# openbook_schematic.net
KiCad netlist of a schematic drawn in EAGLE
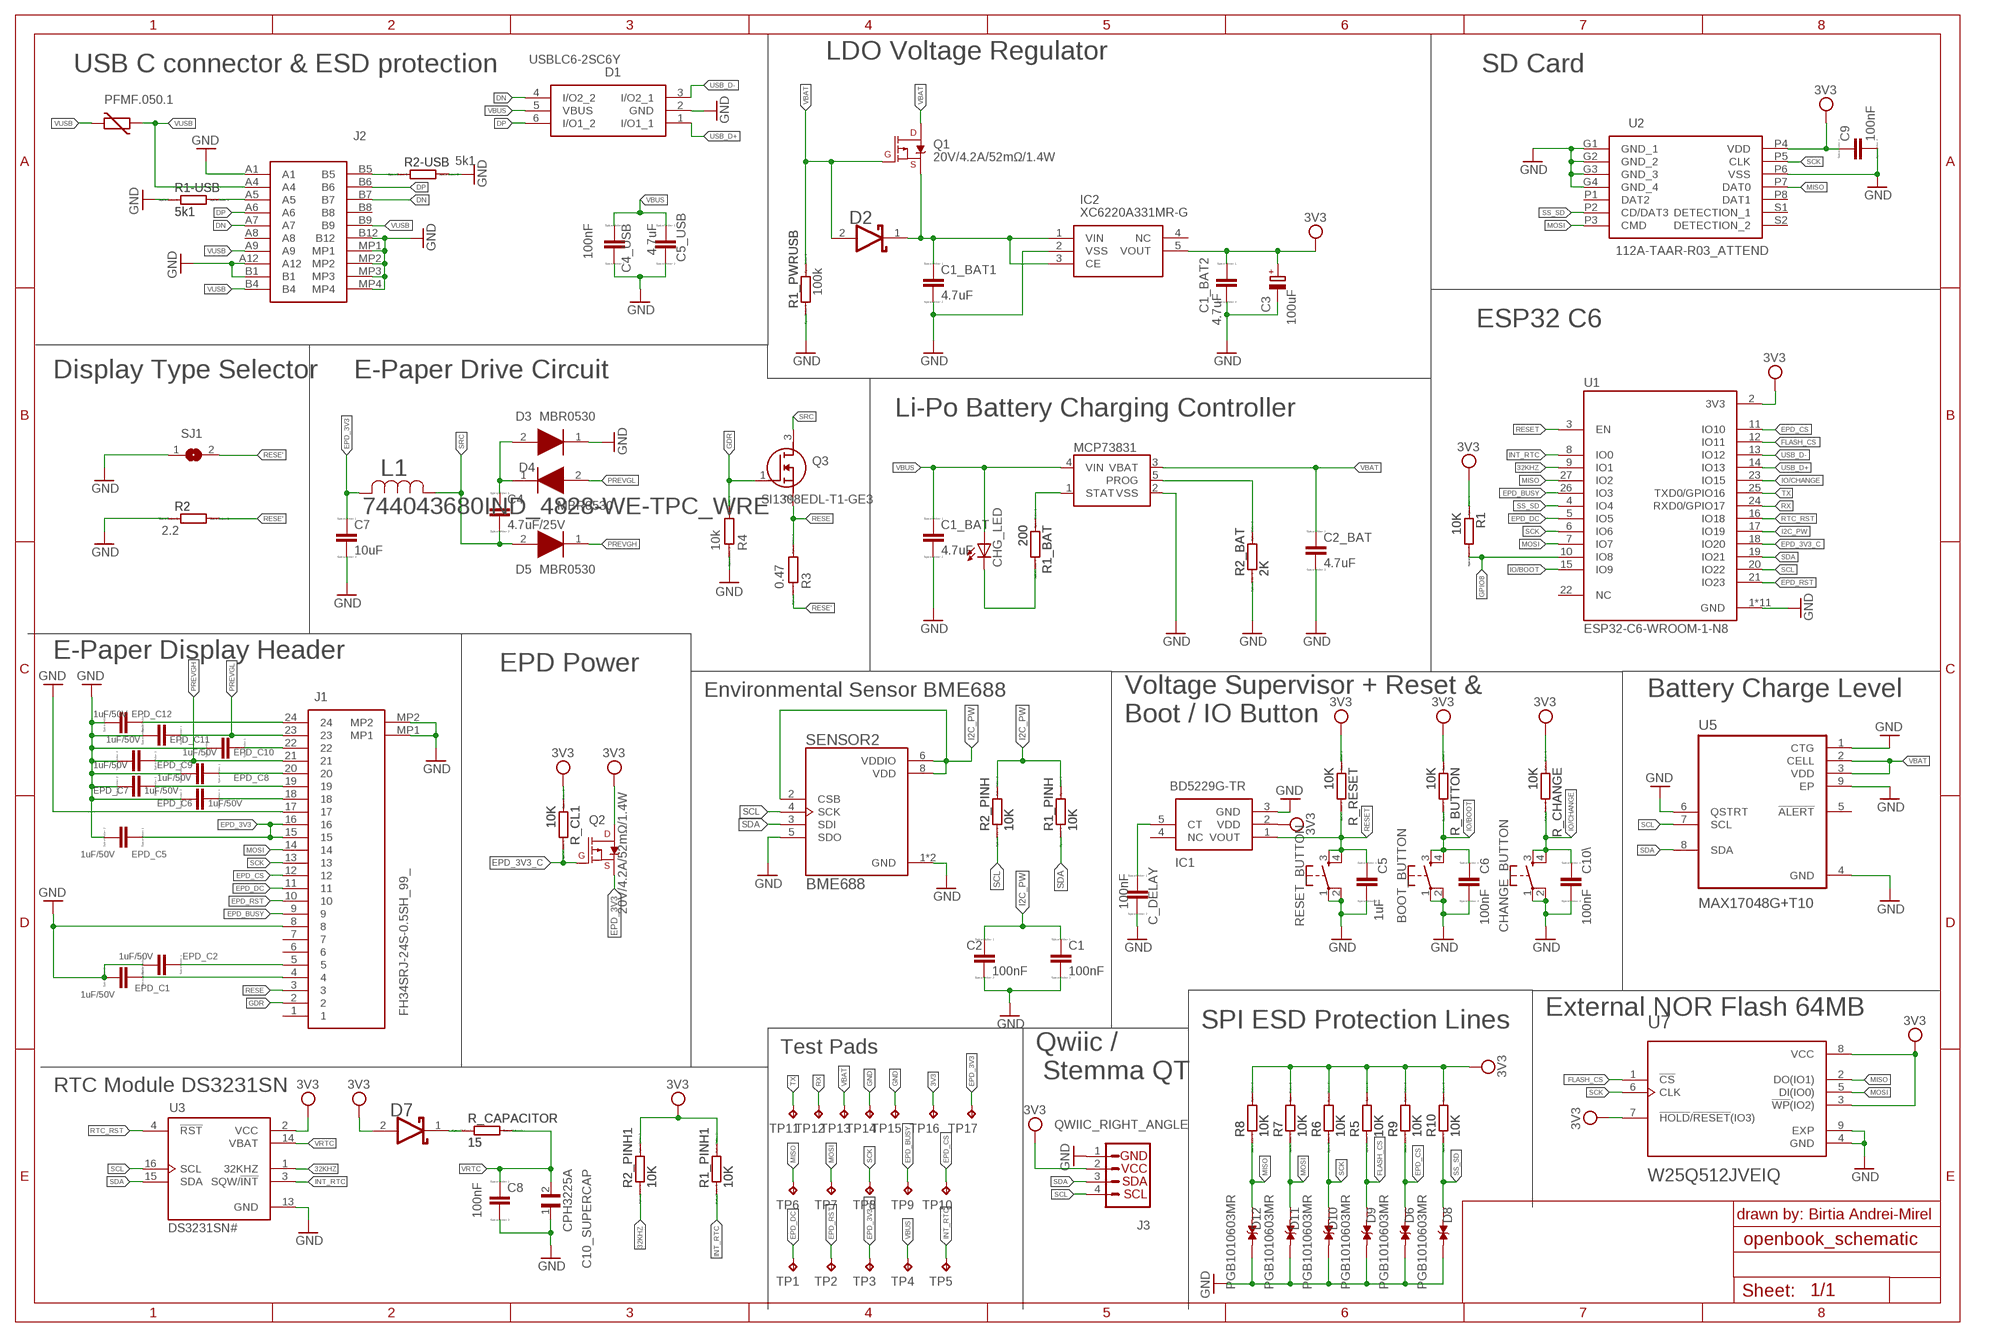
[diagram p0: schematic, sheet 1]

(export (version "E")
  (design (tool "Eeschema 10.0.6"))
  (components
    (comp (ref "BOOT_BUTTON")
      (value "BUTTON_CUSYOMV1")
      (footprint "eagle-import:MYBUTTON")
      (libsource (lib "eagle-import") (part "BUTTON_CUSYOMV1"))
    )
    (comp (ref "C1")
      (value "100nF")
      (footprint "eagle-import:EAGLE-LTSPICE_C0402")
      (libsource (lib "eagle-import") (part "EAGLE-LTSPICE_CC0402"))
    )
    (comp (ref "C1_BAT")
      (value "4.7uF")
      (footprint "eagle-import:EAGLE-LTSPICE_C0402")
      (libsource (lib "eagle-import") (part "EAGLE-LTSPICE_CC0402"))
    )
    (comp (ref "C1_BAT1")
      (value "4.7uF")
      (footprint "eagle-import:EAGLE-LTSPICE_C0402")
      (libsource (lib "eagle-import") (part "EAGLE-LTSPICE_CC0402"))
    )
    (comp (ref "C1_BAT2")
      (value "4.7uF")
      (footprint "eagle-import:EAGLE-LTSPICE_C0402")
      (libsource (lib "eagle-import") (part "EAGLE-LTSPICE_CC0402"))
    )
    (comp (ref "C2")
      (value "100nF")
      (footprint "eagle-import:EAGLE-LTSPICE_C0402")
      (libsource (lib "eagle-import") (part "EAGLE-LTSPICE_CC0402"))
    )
    (comp (ref "C2_BAT")
      (value "4.7uF")
      (footprint "eagle-import:EAGLE-LTSPICE_C0402")
      (libsource (lib "eagle-import") (part "EAGLE-LTSPICE_CC0402"))
    )
    (comp (ref "C3")
      (value "100uF")
      (footprint "eagle-import:RCL_CT3528")
      (libsource (lib "eagle-import") (part "RCL_CPOL-EUCT3528"))
    )
    (comp (ref "C4")
      (value "4.7uF/25V")
      (footprint "eagle-import:EAGLE-LTSPICE_C0402")
      (libsource (lib "eagle-import") (part "EAGLE-LTSPICE_CC0402"))
    )
    (comp (ref "C4_USB")
      (value "100nF")
      (footprint "eagle-import:EAGLE-LTSPICE_C0402")
      (libsource (lib "eagle-import") (part "EAGLE-LTSPICE_CC0402"))
    )
    (comp (ref "C5")
      (value "1uF")
      (footprint "eagle-import:EAGLE-LTSPICE_C0402")
      (libsource (lib "eagle-import") (part "EAGLE-LTSPICE_CC0402"))
    )
    (comp (ref "C5_USB")
      (value "4.7uF")
      (footprint "eagle-import:EAGLE-LTSPICE_C0402")
      (libsource (lib "eagle-import") (part "EAGLE-LTSPICE_CC0402"))
    )
    (comp (ref "C6")
      (value "100nF")
      (footprint "eagle-import:EAGLE-LTSPICE_C0402")
      (libsource (lib "eagle-import") (part "EAGLE-LTSPICE_CC0402"))
    )
    (comp (ref "C7")
      (value "10uF")
      (footprint "eagle-import:EAGLE-LTSPICE_C0402")
      (libsource (lib "eagle-import") (part "EAGLE-LTSPICE_CC0402"))
    )
    (comp (ref "C8")
      (value "100nF")
      (footprint "eagle-import:EAGLE-LTSPICE_C0402")
      (libsource (lib "eagle-import") (part "EAGLE-LTSPICE_CC0402"))
    )
    (comp (ref "C9")
      (value "100nF")
      (footprint "eagle-import:EAGLE-LTSPICE_C0402")
      (libsource (lib "eagle-import") (part "EAGLE-LTSPICE_CC0402"))
    )
    (comp (ref "C10\\")
      (value "100nF")
      (footprint "eagle-import:EAGLE-LTSPICE_C0402")
      (libsource (lib "eagle-import") (part "EAGLE-LTSPICE_CC0402"))
    )
    (comp (ref "C10_SUPERCAP")
      (value "CPH3225A")
      (footprint "eagle-import:CAPCP3225X100N")
      (fields (field (name "MF") "Seiko Instruments"))
      (libsource (lib "eagle-import") (part "CPH3225A"))
    )
    (comp (ref "CHANGE_BUTTON")
      (value "BUTTON_CUSYOMV1")
      (footprint "eagle-import:MYBUTTON")
      (libsource (lib "eagle-import") (part "BUTTON_CUSYOMV1"))
    )
    (comp (ref "CHG_LED")
      (value "ADAFRUIT_LEDCHIP-LED0603")
      (footprint "eagle-import:ADAFRUIT_CHIP-LED0603")
      (libsource (lib "eagle-import") (part "ADAFRUIT_LEDCHIP-LED0603"))
    )
    (comp (ref "C_DELAY")
      (value "100nF")
      (footprint "eagle-import:EAGLE-LTSPICE_C0402")
      (libsource (lib "eagle-import") (part "EAGLE-LTSPICE_CC0402"))
    )
    (comp (ref "D1")
      (value "USBLC6-2SC6Y")
      (footprint "eagle-import:SOT95P280X145-6N")
      (fields (field (name "MF") "STMicroelectronics"))
      (libsource (lib "eagle-import") (part "USBLC6-2SC6Y"))
    )
    (comp (ref "D2")
      (value "ESP32_WROVER_AVX---SD0805S020S1R0_AVX_SD0805S020S1R0_0_0AVX_SD0805S020S1R0_0_0")
      (footprint "eagle-import:ESP32_WROVER_AVX---SD0805S020S1R0_AVX_SD0805S020S1R0_0")
      (fields
        (field (name "DIGIKEY_PART_NUMBER") "478-7800-1-ND")
        (field (name "MF") "AVX")
        (field (name "MOUSER_PART_NUMBER") "581-SD0805S020S1R0")
      )
      (libsource (lib "eagle-import") (part "ESP32_WROVER_AVX---SD0805S020S1R0_AVX_SD0805S020S1R0_0_0AVX_SD0805S020S1R0_0_0"))
    )
    (comp (ref "D3")
      (value "MBR0530")
      (footprint "eagle-import:SOD3716X135N")
      (fields (field (name "MF") "ON Semiconductor"))
      (libsource (lib "eagle-import") (part "MBR0530"))
    )
    (comp (ref "D4")
      (value "MBR0530")
      (footprint "eagle-import:SOD3716X135N")
      (fields (field (name "MF") "ON Semiconductor"))
      (libsource (lib "eagle-import") (part "MBR0530"))
    )
    (comp (ref "D5")
      (value "MBR0530")
      (footprint "eagle-import:SOD3716X135N")
      (fields (field (name "MF") "ON Semiconductor"))
      (libsource (lib "eagle-import") (part "MBR0530"))
    )
    (comp (ref "D6")
      (value "PGB1010603MR")
      (footprint "eagle-import:DIOC1608X36N")
      (fields (field (name "MF") "Littelfuse Inc."))
      (libsource (lib "eagle-import") (part "PGB1010603MR"))
    )
    (comp (ref "D7")
      (value "ESP32_WROVER_AVX---SD0805S020S1R0_AVX_SD0805S020S1R0_0_0AVX_SD0805S020S1R0_0_0")
      (footprint "eagle-import:ESP32_WROVER_AVX---SD0805S020S1R0_AVX_SD0805S020S1R0_0")
      (fields
        (field (name "DIGIKEY_PART_NUMBER") "478-7800-1-ND")
        (field (name "MF") "AVX")
        (field (name "MOUSER_PART_NUMBER") "581-SD0805S020S1R0")
      )
      (libsource (lib "eagle-import") (part "ESP32_WROVER_AVX---SD0805S020S1R0_AVX_SD0805S020S1R0_0_0AVX_SD0805S020S1R0_0_0"))
    )
    (comp (ref "D8")
      (value "PGB1010603MR")
      (footprint "eagle-import:DIOC1608X36N")
      (fields (field (name "MF") "Littelfuse Inc."))
      (libsource (lib "eagle-import") (part "PGB1010603MR"))
    )
    (comp (ref "D9")
      (value "PGB1010603MR")
      (footprint "eagle-import:DIOC1608X36N")
      (fields (field (name "MF") "Littelfuse Inc."))
      (libsource (lib "eagle-import") (part "PGB1010603MR"))
    )
    (comp (ref "D10")
      (value "PGB1010603MR")
      (footprint "eagle-import:DIOC1608X36N")
      (fields (field (name "MF") "Littelfuse Inc."))
      (libsource (lib "eagle-import") (part "PGB1010603MR"))
    )
    (comp (ref "D11")
      (value "PGB1010603MR")
      (footprint "eagle-import:DIOC1608X36N")
      (fields (field (name "MF") "Littelfuse Inc."))
      (libsource (lib "eagle-import") (part "PGB1010603MR"))
    )
    (comp (ref "D12")
      (value "PGB1010603MR")
      (footprint "eagle-import:DIOC1608X36N")
      (fields (field (name "MF") "Littelfuse Inc."))
      (libsource (lib "eagle-import") (part "PGB1010603MR"))
    )
    (comp (ref "EPD_C1")
      (value "1uF/50V")
      (footprint "eagle-import:EAGLE-LTSPICE_C0402")
      (libsource (lib "eagle-import") (part "EAGLE-LTSPICE_CC0402"))
    )
    (comp (ref "EPD_C2")
      (value "1uF/50V")
      (footprint "eagle-import:EAGLE-LTSPICE_C0402")
      (libsource (lib "eagle-import") (part "EAGLE-LTSPICE_CC0402"))
    )
    (comp (ref "EPD_C5")
      (value "1uF/50V")
      (footprint "eagle-import:EAGLE-LTSPICE_C0402")
      (libsource (lib "eagle-import") (part "EAGLE-LTSPICE_CC0402"))
    )
    (comp (ref "EPD_C6")
      (value "1uF/50V")
      (footprint "eagle-import:EAGLE-LTSPICE_C0402")
      (libsource (lib "eagle-import") (part "EAGLE-LTSPICE_CC0402"))
    )
    (comp (ref "EPD_C7")
      (value "1uF/50V")
      (footprint "eagle-import:EAGLE-LTSPICE_C0402")
      (libsource (lib "eagle-import") (part "EAGLE-LTSPICE_CC0402"))
    )
    (comp (ref "EPD_C8")
      (value "1uF/50V")
      (footprint "eagle-import:EAGLE-LTSPICE_C0402")
      (libsource (lib "eagle-import") (part "EAGLE-LTSPICE_CC0402"))
    )
    (comp (ref "EPD_C9")
      (value "1uF/50V")
      (footprint "eagle-import:EAGLE-LTSPICE_C0402")
      (libsource (lib "eagle-import") (part "EAGLE-LTSPICE_CC0402"))
    )
    (comp (ref "EPD_C10")
      (value "1uF/50V")
      (footprint "eagle-import:EAGLE-LTSPICE_C0402")
      (libsource (lib "eagle-import") (part "EAGLE-LTSPICE_CC0402"))
    )
    (comp (ref "EPD_C11")
      (value "1uF/50V")
      (footprint "eagle-import:EAGLE-LTSPICE_C0402")
      (libsource (lib "eagle-import") (part "EAGLE-LTSPICE_CC0402"))
    )
    (comp (ref "EPD_C12")
      (value "1uF/50V")
      (footprint "eagle-import:EAGLE-LTSPICE_C0402")
      (libsource (lib "eagle-import") (part "EAGLE-LTSPICE_CC0402"))
    )
    (comp (ref "IC1")
      (value "BD5229G-TR")
      (footprint "eagle-import:SOT95P280X125-5N")
      (fields (field (name "MOUSER_PART_NUMBER") "755-BD5229G-TR"))
      (libsource (lib "eagle-import") (part "BD5229G-TR"))
    )
    (comp (ref "IC2")
      (value "XC6220A331MR-G")
      (footprint "eagle-import:SOT95P280X120-5N")
      (fields (field (name "MOUSER_PART_NUMBER") "865-XC6220A331MR-G"))
      (libsource (lib "eagle-import") (part "XC6220A331MR-G"))
    )
    (comp (ref "J1")
      (value "FH34SRJ-24S-0.5SH_99_")
      (footprint "eagle-import:FH34SRJ24S05SH99")
      (fields
        (field (name "MANUFACTURER_PART_NUMBER") "FH34SRJ-24S-0.5SH(99)")
        (field (name "MOUSER_PART_NUMBER") "798-FH34SRJ24S05SH99")
      )
      (libsource (lib "eagle-import") (part "FH34SRJ-24S-0.5SH_99_"))
    )
    (comp (ref "J2")
      (value "SAMACSYS_PARTS_USB4110-GF-A")
      (footprint "eagle-import:SAMACSYS_PARTS_USB4110GFA")
      (fields
        (field (name "MANUFACTURER_PART_NUMBER") "USB4110-GF-A")
        (field (name "MOUSER_PART_NUMBER") "640-USB4110-GF-A")
      )
      (libsource (lib "eagle-import") (part "SAMACSYS_PARTS_USB4110-GF-A"))
    )
    (comp (ref "J3")
      (value "QWIIC_RIGHT_ANGLE")
      (footprint "eagle-import:JST04_1MM_RA")
      (libsource (lib "eagle-import") (part "QWIIC_CONNECTORJS-1MM"))
    )
    (comp (ref "L1")
      (value "744043680IND_4828-WE-TPC_WRE")
      (footprint "eagle-import:IND_4828-WE-TPC_WRE")
      (fields
        (field (name "MANUFACTURER_PART_NUMBER") "744043680")
        (field (name "COPYRIGHT") "Copyright (C) 2024 Ultra Librarian. All rights reserved.")
      )
      (libsource (lib "eagle-import") (part "744043680IND_4828-WE-TPC_WRE"))
    )
    (comp (ref "MCP73831")
      (value "ESP32_WROVER_SPARKFUN-IC-POWER_MCP73831")
      (footprint "eagle-import:ESP32_WROVER_SPARKFUN-IC-POWER_SOT23-5")
      (libsource (lib "eagle-import") (part "ESP32_WROVER_SPARKFUN-IC-POWER_MCP73831"))
    )
    (comp (ref "PFMF.050.1")
      (value "ESP32C6_VARISTORCN1812")
      (footprint "eagle-import:ESP32C6_VARISTOR_CT_CN1812")
      (libsource (lib "eagle-import") (part "ESP32C6_VARISTORCN1812"))
    )
    (comp (ref "Q1")
      (value "20V/4.2A/52mΩ/1.4W")
      (footprint "eagle-import:ESP32_WROVER_SPARKFUN-DISCRETESEMI_SOT23-3")
      (libsource (lib "eagle-import") (part "ESP32_WROVER_SPARKFUN-DISCRETESEMI_MOSFET_PCH-DMG2305UX-7"))
    )
    (comp (ref "Q2")
      (value "20V/4.2A/52mΩ/1.4W")
      (footprint "eagle-import:ESP32_WROVER_SPARKFUN-DISCRETESEMI_SOT23-3")
      (libsource (lib "eagle-import") (part "ESP32_WROVER_SPARKFUN-DISCRETESEMI_MOSFET_PCH-DMG2305UX-7"))
    )
    (comp (ref "Q3")
      (value "SI1308EDL-T1-GE3")
      (footprint "eagle-import:SOT65P210X110-3N")
      (fields (field (name "MF") "Vishay Siliconix"))
      (libsource (lib "eagle-import") (part "SI1308EDL-T1-GE3"))
    )
    (comp (ref "R1")
      (value "10K")
      (footprint "eagle-import:ESP32_WROVER_EAGLE-LTSPICE_R0402")
      (libsource (lib "eagle-import") (part "ESP32_WROVER_EAGLE-LTSPICE_RR0402"))
    )
    (comp (ref "R1-USB")
      (value "5k1")
      (footprint "eagle-import:ESP32_WROVER_EAGLE-LTSPICE_R0402")
      (libsource (lib "eagle-import") (part "ESP32_WROVER_EAGLE-LTSPICE_RR0402"))
    )
    (comp (ref "R1_BAT")
      (value "200")
      (footprint "eagle-import:ESP32_WROVER_EAGLE-LTSPICE_R0402")
      (libsource (lib "eagle-import") (part "ESP32_WROVER_EAGLE-LTSPICE_RR0402"))
    )
    (comp (ref "R1_PINH")
      (value "10K")
      (footprint "eagle-import:ESP32_WROVER_EAGLE-LTSPICE_R0402")
      (libsource (lib "eagle-import") (part "ESP32_WROVER_EAGLE-LTSPICE_RR0402"))
    )
    (comp (ref "R1_PINH1")
      (value "10K")
      (footprint "eagle-import:ESP32_WROVER_EAGLE-LTSPICE_R0402")
      (libsource (lib "eagle-import") (part "ESP32_WROVER_EAGLE-LTSPICE_RR0402"))
    )
    (comp (ref "R1_PWRUSB")
      (value "100k")
      (footprint "eagle-import:ESP32_WROVER_EAGLE-LTSPICE_R0402")
      (libsource (lib "eagle-import") (part "ESP32_WROVER_EAGLE-LTSPICE_RR0402"))
    )
    (comp (ref "R2")
      (value "2.2")
      (footprint "eagle-import:ESP32_WROVER_EAGLE-LTSPICE_R0402")
      (libsource (lib "eagle-import") (part "ESP32_WROVER_EAGLE-LTSPICE_RR0402"))
    )
    (comp (ref "R2-USB")
      (value "5k1")
      (footprint "eagle-import:ESP32_WROVER_EAGLE-LTSPICE_R0402")
      (libsource (lib "eagle-import") (part "ESP32_WROVER_EAGLE-LTSPICE_RR0402"))
    )
    (comp (ref "R2_BAT")
      (value "2K")
      (footprint "eagle-import:ESP32_WROVER_EAGLE-LTSPICE_R0402")
      (libsource (lib "eagle-import") (part "ESP32_WROVER_EAGLE-LTSPICE_RR0402"))
    )
    (comp (ref "R2_PINH")
      (value "10K")
      (footprint "eagle-import:ESP32_WROVER_EAGLE-LTSPICE_R0402")
      (libsource (lib "eagle-import") (part "ESP32_WROVER_EAGLE-LTSPICE_RR0402"))
    )
    (comp (ref "R2_PINH1")
      (value "10K")
      (footprint "eagle-import:ESP32_WROVER_EAGLE-LTSPICE_R0402")
      (libsource (lib "eagle-import") (part "ESP32_WROVER_EAGLE-LTSPICE_RR0402"))
    )
    (comp (ref "R3")
      (value "0.47")
      (footprint "eagle-import:ESP32_WROVER_EAGLE-LTSPICE_R0402")
      (libsource (lib "eagle-import") (part "ESP32_WROVER_EAGLE-LTSPICE_RR0402"))
    )
    (comp (ref "R4")
      (value "10k")
      (footprint "eagle-import:ESP32_WROVER_EAGLE-LTSPICE_R0402")
      (libsource (lib "eagle-import") (part "ESP32_WROVER_EAGLE-LTSPICE_RR0402"))
    )
    (comp (ref "R5")
      (value "10K")
      (footprint "eagle-import:ESP32_WROVER_EAGLE-LTSPICE_R0402")
      (libsource (lib "eagle-import") (part "ESP32_WROVER_EAGLE-LTSPICE_RR0402"))
    )
    (comp (ref "R6")
      (value "10K")
      (footprint "eagle-import:ESP32_WROVER_EAGLE-LTSPICE_R0402")
      (libsource (lib "eagle-import") (part "ESP32_WROVER_EAGLE-LTSPICE_RR0402"))
    )
    (comp (ref "R7")
      (value "10K")
      (footprint "eagle-import:ESP32_WROVER_EAGLE-LTSPICE_R0402")
      (libsource (lib "eagle-import") (part "ESP32_WROVER_EAGLE-LTSPICE_RR0402"))
    )
    (comp (ref "R8")
      (value "10K")
      (footprint "eagle-import:ESP32_WROVER_EAGLE-LTSPICE_R0402")
      (libsource (lib "eagle-import") (part "ESP32_WROVER_EAGLE-LTSPICE_RR0402"))
    )
    (comp (ref "R9")
      (value "10K")
      (footprint "eagle-import:ESP32_WROVER_EAGLE-LTSPICE_R0402")
      (libsource (lib "eagle-import") (part "ESP32_WROVER_EAGLE-LTSPICE_RR0402"))
    )
    (comp (ref "R10")
      (value "10K")
      (footprint "eagle-import:ESP32_WROVER_EAGLE-LTSPICE_R0402")
      (libsource (lib "eagle-import") (part "ESP32_WROVER_EAGLE-LTSPICE_RR0402"))
    )
    (comp (ref "RESET_BUTTON")
      (value "BUTTON_CUSYOMV1")
      (footprint "eagle-import:MYBUTTON")
      (libsource (lib "eagle-import") (part "BUTTON_CUSYOMV1"))
    )
    (comp (ref "R_BUTTON")
      (value "10K")
      (footprint "eagle-import:ESP32_WROVER_EAGLE-LTSPICE_R0402")
      (libsource (lib "eagle-import") (part "ESP32_WROVER_EAGLE-LTSPICE_RR0402"))
    )
    (comp (ref "R_CAPACITOR")
      (value "15")
      (footprint "eagle-import:ESP32_WROVER_EAGLE-LTSPICE_R0402")
      (libsource (lib "eagle-import") (part "ESP32_WROVER_EAGLE-LTSPICE_RR0402"))
    )
    (comp (ref "R_CHANGE")
      (value "10K")
      (footprint "eagle-import:ESP32_WROVER_EAGLE-LTSPICE_R0402")
      (libsource (lib "eagle-import") (part "ESP32_WROVER_EAGLE-LTSPICE_RR0402"))
    )
    (comp (ref "R_CL1")
      (value "10K")
      (footprint "eagle-import:ESP32_WROVER_EAGLE-LTSPICE_R0402")
      (libsource (lib "eagle-import") (part "ESP32_WROVER_EAGLE-LTSPICE_RR0402"))
    )
    (comp (ref "R_RESET")
      (value "10K")
      (footprint "eagle-import:ESP32_WROVER_EAGLE-LTSPICE_R0402")
      (libsource (lib "eagle-import") (part "ESP32_WROVER_EAGLE-LTSPICE_RR0402"))
    )
    (comp (ref "SENSOR2")
      (value "BME688")
      (footprint "eagle-import:ESP32_WROVER_BME680_PSON80P300X300X100-8N")
      (fields (field (name "MF") "Bosch Sensortec") (field (name "MP") "BME680"))
      (libsource (lib "eagle-import") (part "ESP32_WROVER_BME680_BME680"))
    )
    (comp (ref "SJ1") (value "SJ") (footprint "eagle-import:SJ") (libsource (lib "eagle-import") (part "SJ")))
    (comp (ref "TP1")
      (value "TPTP20R")
      (footprint "eagle-import:TP20R")
      (libsource (lib "eagle-import") (part "TPTP20R"))
    )
    (comp (ref "TP2")
      (value "TPTP20R")
      (footprint "eagle-import:TP20R")
      (libsource (lib "eagle-import") (part "TPTP20R"))
    )
    (comp (ref "TP3")
      (value "TPTP20R")
      (footprint "eagle-import:TP20R")
      (libsource (lib "eagle-import") (part "TPTP20R"))
    )
    (comp (ref "TP4")
      (value "TPTP20R")
      (footprint "eagle-import:TP20R")
      (libsource (lib "eagle-import") (part "TPTP20R"))
    )
    (comp (ref "TP5")
      (value "TPTP20R")
      (footprint "eagle-import:TP20R")
      (libsource (lib "eagle-import") (part "TPTP20R"))
    )
    (comp (ref "TP6")
      (value "TPTP20R")
      (footprint "eagle-import:TP20R")
      (libsource (lib "eagle-import") (part "TPTP20R"))
    )
    (comp (ref "TP7")
      (value "TPTP20R")
      (footprint "eagle-import:TP20R")
      (libsource (lib "eagle-import") (part "TPTP20R"))
    )
    (comp (ref "TP8")
      (value "TPTP20R")
      (footprint "eagle-import:TP20R")
      (libsource (lib "eagle-import") (part "TPTP20R"))
    )
    (comp (ref "TP9")
      (value "TPTP20R")
      (footprint "eagle-import:TP20R")
      (libsource (lib "eagle-import") (part "TPTP20R"))
    )
    (comp (ref "TP10")
      (value "TPTP20R")
      (footprint "eagle-import:TP20R")
      (libsource (lib "eagle-import") (part "TPTP20R"))
    )
    (comp (ref "TP11")
      (value "TPTP20R")
      (footprint "eagle-import:TP20R")
      (libsource (lib "eagle-import") (part "TPTP20R"))
    )
    (comp (ref "TP12")
      (value "TPTP20R")
      (footprint "eagle-import:TP20R")
      (libsource (lib "eagle-import") (part "TPTP20R"))
    )
    (comp (ref "TP13")
      (value "TPTP20R")
      (footprint "eagle-import:TP20R")
      (libsource (lib "eagle-import") (part "TPTP20R"))
    )
    (comp (ref "TP14")
      (value "TPTP20R")
      (footprint "eagle-import:TP20R")
      (libsource (lib "eagle-import") (part "TPTP20R"))
    )
    (comp (ref "TP15")
      (value "TPTP20R")
      (footprint "eagle-import:TP20R")
      (libsource (lib "eagle-import") (part "TPTP20R"))
    )
    (comp (ref "TP16")
      (value "TPTP20R")
      (footprint "eagle-import:TP20R")
      (libsource (lib "eagle-import") (part "TPTP20R"))
    )
    (comp (ref "TP17")
      (value "TPTP20R")
      (footprint "eagle-import:TP20R")
      (libsource (lib "eagle-import") (part "TPTP20R"))
    )
    (comp (ref "U1")
      (value "ESP32-C6-WROOM-1-N8")
      (footprint "eagle-import:XCVR_ESP32-C6-WROOM-1-N8")
      (fields (field (name "MF") "Espressif Systems"))
      (libsource (lib "eagle-import") (part "ESP32-C6-WROOM-1-N8"))
    )
    (comp (ref "U2")
      (value "112A-TAAR-R03_ATTEND")
      (footprint "eagle-import:112ATAARR03ATTEND")
      (fields (field (name "MANUFACTURER_PART_NUMBER") "112A-TAAR-R03 ATTEND"))
      (libsource (lib "eagle-import") (part "112A-TAAR-R03_ATTEND"))
    )
    (comp (ref "U3")
      (value "DS3231SN#")
      (footprint "eagle-import:SOIC127P1032X265-16N")
      (fields (field (name "MF") "Analog Devices"))
      (libsource (lib "eagle-import") (part "DS3231SN#"))
    )
    (comp (ref "U5")
      (value "MAX17048G+T10")
      (footprint "eagle-import:SON50P200X200X80-9N")
      (fields (field (name "MF") "Analog Devices"))
      (libsource (lib "eagle-import") (part "MAX17048G+T10"))
    )
    (comp (ref "U7")
      (value "W25Q512JVEIQ")
      (footprint "eagle-import:SON127P600X800X80-9N")
      (fields (field (name "MF") "Winbond Electronics"))
      (libsource (lib "eagle-import") (part "W25Q512JVEIQ"))
    )
  )
  (nets
    (net (code "1") (name "3V3") (class "Default")
      (node (ref "C1_BAT2") (pin "1") (pinfunction "1_1") (pintype "passive"))
      (node (ref "C3") (pin "+") (pinfunction "+_+") (pintype "passive"))
      (node (ref "C9") (pin "1") (pinfunction "1_1") (pintype "passive"))
      (node (ref "D7") (pin "2") (pinfunction "ANODE_2") (pintype "bidirectional"))
      (node (ref "IC1") (pin "2") (pinfunction "VDD_2") (pintype "bidirectional"))
      (node (ref "IC2") (pin "5") (pinfunction "VOUT_5") (pintype "bidirectional"))
      (node (ref "J3") (pin "2") (pinfunction "2_2") (pintype "power_in"))
      (node (ref "Q2") (pin "3") (pinfunction "D_3") (pintype "bidirectional"))
      (node (ref "R1") (pin "1") (pinfunction "1_1") (pintype "passive"))
      (node (ref "R10") (pin "2") (pinfunction "2_2") (pintype "passive"))
      (node (ref "R1_PINH1") (pin "2") (pinfunction "2_2") (pintype "passive"))
      (node (ref "R2_PINH1") (pin "2") (pinfunction "2_2") (pintype "passive"))
      (node (ref "R5") (pin "2") (pinfunction "2_2") (pintype "passive"))
      (node (ref "R6") (pin "2") (pinfunction "2_2") (pintype "passive"))
      (node (ref "R7") (pin "2") (pinfunction "2_2") (pintype "passive"))
      (node (ref "R8") (pin "2") (pinfunction "2_2") (pintype "passive"))
      (node (ref "R9") (pin "2") (pinfunction "2_2") (pintype "passive"))
      (node (ref "R_BUTTON") (pin "1") (pinfunction "1_1") (pintype "passive"))
      (node (ref "R_CHANGE") (pin "1") (pinfunction "1_1") (pintype "passive"))
      (node (ref "R_CL1") (pin "1") (pinfunction "1_1") (pintype "passive"))
      (node (ref "R_RESET") (pin "1") (pinfunction "1_1") (pintype "passive"))
      (node (ref "TP16") (pin "TP") (pinfunction "TP_TP") (pintype "input"))
      (node (ref "U1") (pin "2") (pinfunction "3V3_2") (pintype "power_in"))
      (node (ref "U2") (pin "P4") (pinfunction "VDD_P4") (pintype "bidirectional"))
      (node (ref "U3") (pin "2") (pinfunction "VCC_2") (pintype "power_in"))
      (node (ref "U7") (pin "3") (pinfunction "~{WP}(IO2)_3") (pintype "bidirectional"))
      (node (ref "U7") (pin "7") (pinfunction "~{HOLD}/~{RESET}(IO3)_7") (pintype "bidirectional"))
      (node (ref "U7") (pin "8") (pinfunction "VCC_8") (pintype "power_in"))
    )
    (net (code "2") (name "32KHZ") (class "Default")
      (node (ref "R2_PINH1") (pin "1") (pinfunction "1_1") (pintype "passive"))
      (node (ref "U1") (pin "9") (pinfunction "IO1_9") (pintype "bidirectional"))
      (node (ref "U3") (pin "1") (pinfunction "32KHZ_1") (pintype "output"))
    )
    (net (code "3") (name "DN") (class "Default")
      (node (ref "D1") (pin "4") (pinfunction "I/O2_2_4") (pintype "bidirectional"))
      (node (ref "J2") (pin "A7") (pinfunction "A7_A7") (pintype "bidirectional"))
      (node (ref "J2") (pin "B7") (pinfunction "B7_B7") (pintype "bidirectional"))
    )
    (net (code "4") (name "DP") (class "Default")
      (node (ref "D1") (pin "6") (pinfunction "I/O1_2_6") (pintype "bidirectional"))
      (node (ref "J2") (pin "A6") (pinfunction "A6_A6") (pintype "bidirectional"))
      (node (ref "J2") (pin "B6") (pinfunction "B6_B6") (pintype "bidirectional"))
    )
    (net (code "5") (name "EPD_3V3") (class "Default")
      (node (ref "C7") (pin "1") (pinfunction "1_1") (pintype "passive"))
      (node (ref "EPD_C5") (pin "1") (pinfunction "1_1") (pintype "passive"))
      (node (ref "J1") (pin "15") (pinfunction "15_15") (pintype "bidirectional"))
      (node (ref "J1") (pin "16") (pinfunction "16_16") (pintype "bidirectional"))
      (node (ref "L1") (pin "2") (pinfunction "2_2") (pintype "passive"))
      (node (ref "Q2") (pin "2") (pinfunction "S_2") (pintype "bidirectional"))
      (node (ref "TP17") (pin "TP") (pinfunction "TP_TP") (pintype "input"))
    )
    (net (code "6") (name "EPD_3V3_C") (class "Default")
      (node (ref "Q2") (pin "1") (pinfunction "G_1") (pintype "bidirectional"))
      (node (ref "R_CL1") (pin "2") (pinfunction "2_2") (pintype "passive"))
      (node (ref "TP3") (pin "TP") (pinfunction "TP_TP") (pintype "input"))
      (node (ref "U1") (pin "18") (pinfunction "IO20_18") (pintype "bidirectional"))
    )
    (net (code "7") (name "EPD_BUSY") (class "Default")
      (node (ref "J1") (pin "9") (pinfunction "9_9") (pintype "bidirectional"))
      (node (ref "TP9") (pin "TP") (pinfunction "TP_TP") (pintype "input"))
      (node (ref "U1") (pin "26") (pinfunction "IO3_26") (pintype "bidirectional"))
    )
    (net (code "8") (name "EPD_CS") (class "Default")
      (node (ref "D6") (pin "1") (pinfunction "1_1") (pintype "passive"))
      (node (ref "J1") (pin "12") (pinfunction "12_12") (pintype "bidirectional"))
      (node (ref "R9") (pin "1") (pinfunction "1_1") (pintype "passive"))
      (node (ref "TP10") (pin "TP") (pinfunction "TP_TP") (pintype "input"))
      (node (ref "U1") (pin "11") (pinfunction "IO10_11") (pintype "bidirectional"))
    )
    (net (code "9") (name "EPD_DC") (class "Default")
      (node (ref "J1") (pin "11") (pinfunction "11_11") (pintype "bidirectional"))
      (node (ref "TP1") (pin "TP") (pinfunction "TP_TP") (pintype "input"))
      (node (ref "U1") (pin "5") (pinfunction "IO5_5") (pintype "bidirectional"))
    )
    (net (code "10") (name "EPD_RST") (class "Default")
      (node (ref "J1") (pin "10") (pinfunction "10_10") (pintype "bidirectional"))
      (node (ref "TP2") (pin "TP") (pinfunction "TP_TP") (pintype "input"))
      (node (ref "U1") (pin "21") (pinfunction "IO23_21") (pintype "bidirectional"))
    )
    (net (code "11") (name "FLASH_CS") (class "Default")
      (node (ref "D9") (pin "1") (pinfunction "1_1") (pintype "passive"))
      (node (ref "R5") (pin "1") (pinfunction "1_1") (pintype "passive"))
      (node (ref "U1") (pin "12") (pinfunction "IO11_12") (pintype "bidirectional"))
      (node (ref "U7") (pin "1") (pinfunction "~{CS}_1") (pintype "input"))
    )
    (net (code "12") (name "GDR") (class "Default")
      (node (ref "J1") (pin "2") (pinfunction "2_2") (pintype "bidirectional"))
      (node (ref "Q3") (pin "1") (pinfunction "G_1") (pintype "bidirectional"))
      (node (ref "R4") (pin "2") (pinfunction "2_2") (pintype "passive"))
    )
    (net (code "13") (name "GND") (class "Default")
      (node (ref "BOOT_BUTTON") (pin "1") (pinfunction "1_1") (pintype "passive"))
      (node (ref "BOOT_BUTTON") (pin "2") (pinfunction "2_2") (pintype "passive"))
      (node (ref "C1") (pin "2") (pinfunction "2_2") (pintype "passive"))
      (node (ref "C10\\") (pin "2") (pinfunction "2_2") (pintype "passive"))
      (node (ref "C10_SUPERCAP") (pin "1") (pinfunction "1_1") (pintype "passive"))
      (node (ref "C1_BAT") (pin "2") (pinfunction "2_2") (pintype "passive"))
      (node (ref "C1_BAT1") (pin "2") (pinfunction "2_2") (pintype "passive"))
      (node (ref "C1_BAT2") (pin "2") (pinfunction "2_2") (pintype "passive"))
      (node (ref "C2") (pin "2") (pinfunction "2_2") (pintype "passive"))
      (node (ref "C2_BAT") (pin "2") (pinfunction "2_2") (pintype "passive"))
      (node (ref "C3") (pin "-") (pinfunction "-_-") (pintype "passive"))
      (node (ref "C4_USB") (pin "2") (pinfunction "2_2") (pintype "passive"))
      (node (ref "C5") (pin "2") (pinfunction "2_2") (pintype "passive"))
      (node (ref "C5_USB") (pin "2") (pinfunction "2_2") (pintype "passive"))
      (node (ref "C6") (pin "2") (pinfunction "2_2") (pintype "passive"))
      (node (ref "C7") (pin "2") (pinfunction "2_2") (pintype "passive"))
      (node (ref "C8") (pin "2") (pinfunction "2_2") (pintype "passive"))
      (node (ref "C9") (pin "2") (pinfunction "2_2") (pintype "passive"))
      (node (ref "CHANGE_BUTTON") (pin "1") (pinfunction "1_1") (pintype "passive"))
      (node (ref "CHANGE_BUTTON") (pin "2") (pinfunction "2_2") (pintype "passive"))
      (node (ref "C_DELAY") (pin "2") (pinfunction "2_2") (pintype "passive"))
      (node (ref "D1") (pin "2") (pinfunction "GND_2") (pintype "bidirectional"))
      (node (ref "D10") (pin "2") (pinfunction "2_2") (pintype "passive"))
      (node (ref "D11") (pin "2") (pinfunction "2_2") (pintype "passive"))
      (node (ref "D12") (pin "2") (pinfunction "2_2") (pintype "passive"))
      (node (ref "D3") (pin "1") (pinfunction "K_1") (pintype "bidirectional"))
      (node (ref "D6") (pin "2") (pinfunction "2_2") (pintype "passive"))
      (node (ref "D8") (pin "2") (pinfunction "2_2") (pintype "passive"))
      (node (ref "D9") (pin "2") (pinfunction "2_2") (pintype "passive"))
      (node (ref "EPD_C1") (pin "2") (pinfunction "2_2") (pintype "passive"))
      (node (ref "EPD_C10") (pin "2") (pinfunction "2_2") (pintype "passive"))
      (node (ref "EPD_C11") (pin "2") (pinfunction "2_2") (pintype "passive"))
      (node (ref "EPD_C12") (pin "2") (pinfunction "2_2") (pintype "passive"))
      (node (ref "EPD_C2") (pin "2") (pinfunction "2_2") (pintype "passive"))
      (node (ref "EPD_C5") (pin "2") (pinfunction "2_2") (pintype "passive"))
      (node (ref "EPD_C6") (pin "2") (pinfunction "2_2") (pintype "passive"))
      (node (ref "EPD_C7") (pin "2") (pinfunction "2_2") (pintype "passive"))
      (node (ref "EPD_C8") (pin "2") (pinfunction "2_2") (pintype "passive"))
      (node (ref "EPD_C9") (pin "2") (pinfunction "2_2") (pintype "passive"))
      (node (ref "IC1") (pin "3") (pinfunction "GND_3") (pintype "bidirectional"))
      (node (ref "IC2") (pin "2") (pinfunction "VSS_2") (pintype "bidirectional"))
      (node (ref "J1") (pin "17") (pinfunction "17_17") (pintype "bidirectional"))
      (node (ref "J1") (pin "8") (pinfunction "8_8") (pintype "bidirectional"))
      (node (ref "J1") (pin "MP1") (pinfunction "MP1_MP1") (pintype "bidirectional"))
      (node (ref "J1") (pin "MP2") (pinfunction "MP2_MP2") (pintype "bidirectional"))
      (node (ref "J2") (pin "A1") (pinfunction "A1_A1") (pintype "bidirectional"))
      (node (ref "J2") (pin "A12") (pinfunction "A12_A12") (pintype "bidirectional"))
      (node (ref "J2") (pin "B1") (pinfunction "B1_B1") (pintype "bidirectional"))
      (node (ref "J2") (pin "B12") (pinfunction "B12_B12") (pintype "bidirectional"))
      (node (ref "J2") (pin "MP1") (pinfunction "MP1_MP1") (pintype "bidirectional"))
      (node (ref "J2") (pin "MP2") (pinfunction "MP2_MP2") (pintype "bidirectional"))
      (node (ref "J2") (pin "MP3") (pinfunction "MP3_MP3") (pintype "bidirectional"))
      (node (ref "J2") (pin "MP4") (pinfunction "MP4_MP4") (pintype "bidirectional"))
      (node (ref "J3") (pin "1") (pinfunction "1_1") (pintype "power_in"))
      (node (ref "MCP73831") (pin "2") (pinfunction "VSS_2") (pintype "power_in"))
      (node (ref "R1-USB") (pin "1") (pinfunction "1_1") (pintype "passive"))
      (node (ref "R1_PWRUSB") (pin "1") (pinfunction "1_1") (pintype "passive"))
      (node (ref "R2") (pin "1") (pinfunction "1_1") (pintype "passive"))
      (node (ref "R2-USB") (pin "2") (pinfunction "2_2") (pintype "passive"))
      (node (ref "R2_BAT") (pin "1") (pinfunction "1_1") (pintype "passive"))
      (node (ref "R4") (pin "1") (pinfunction "1_1") (pintype "passive"))
      (node (ref "RESET_BUTTON") (pin "1") (pinfunction "1_1") (pintype "passive"))
      (node (ref "RESET_BUTTON") (pin "2") (pinfunction "2_2") (pintype "passive"))
      (node (ref "SENSOR2") (pin "1") (pinfunction "GND_1") (pintype "power_in"))
      (node (ref "SENSOR2") (pin "5") (pinfunction "SDO_5") (pintype "bidirectional"))
      (node (ref "SENSOR2") (pin "7") (pinfunction "GND_7") (pintype "power_in"))
      (node (ref "SJ1") (pin "1") (pinfunction "1_1") (pintype "passive"))
      (node (ref "TP14") (pin "TP") (pinfunction "TP_TP") (pintype "input"))
      (node (ref "TP15") (pin "TP") (pinfunction "TP_TP") (pintype "input"))
      (node (ref "U1") (pin "1") (pinfunction "GND_1") (pintype "power_in"))
      (node (ref "U1") (pin "28") (pinfunction "GND_28") (pintype "power_in"))
      (node (ref "U1") (pin "29_1") (pinfunction "GND_29_1") (pintype "power_in"))
      (node (ref "U1") (pin "29_2") (pinfunction "GND_29_2") (pintype "power_in"))
      (node (ref "U1") (pin "29_3") (pinfunction "GND_29_3") (pintype "power_in"))
      (node (ref "U1") (pin "29_4") (pinfunction "GND_29_4") (pintype "power_in"))
      (node (ref "U1") (pin "29_5") (pinfunction "GND_29_5") (pintype "power_in"))
      (node (ref "U1") (pin "29_6") (pinfunction "GND_29_6") (pintype "power_in"))
      (node (ref "U1") (pin "29_7") (pinfunction "GND_29_7") (pintype "power_in"))
      (node (ref "U1") (pin "29_8") (pinfunction "GND_29_8") (pintype "power_in"))
      (node (ref "U1") (pin "29_9") (pinfunction "GND_29_9") (pintype "power_in"))
      (node (ref "U2") (pin "G1") (pinfunction "GND_1_G1") (pintype "bidirectional"))
      (node (ref "U2") (pin "G2") (pinfunction "GND_2_G2") (pintype "bidirectional"))
      (node (ref "U2") (pin "G3") (pinfunction "GND_3_G3") (pintype "bidirectional"))
      (node (ref "U2") (pin "G4") (pinfunction "GND_4_G4") (pintype "bidirectional"))
      (node (ref "U2") (pin "P6") (pinfunction "VSS_P6") (pintype "bidirectional"))
      (node (ref "U3") (pin "13") (pinfunction "GND_13") (pintype "power_in"))
      (node (ref "U5") (pin "1") (pinfunction "CTG_1") (pintype "power_in"))
      (node (ref "U5") (pin "4") (pinfunction "GND_4") (pintype "power_in"))
      (node (ref "U5") (pin "6") (pinfunction "QSTRT_6") (pintype "input"))
      (node (ref "U5") (pin "9") (pinfunction "EP_9") (pintype "power_in"))
      (node (ref "U7") (pin "4") (pinfunction "GND_4") (pintype "power_in"))
      (node (ref "U7") (pin "9") (pinfunction "EXP_9") (pintype "passive"))
    )
    (net (code "14") (name "GPIO8") (class "Default")
      (node (ref "R1") (pin "2") (pinfunction "2_2") (pintype "passive"))
      (node (ref "U1") (pin "10") (pinfunction "IO8_10") (pintype "bidirectional"))
    )
    (net (code "15") (name "I2C_PW") (class "Default")
      (node (ref "C1") (pin "1") (pinfunction "1_1") (pintype "passive"))
      (node (ref "C2") (pin "1") (pinfunction "1_1") (pintype "passive"))
      (node (ref "R1_PINH") (pin "2") (pinfunction "2_2") (pintype "passive"))
      (node (ref "R2_PINH") (pin "2") (pinfunction "2_2") (pintype "passive"))
      (node (ref "SENSOR2") (pin "2") (pinfunction "CSB_2") (pintype "input"))
      (node (ref "SENSOR2") (pin "6") (pinfunction "VDDIO_6") (pintype "power_in"))
      (node (ref "SENSOR2") (pin "8") (pinfunction "VDD_8") (pintype "power_in"))
      (node (ref "U1") (pin "17") (pinfunction "IO19_17") (pintype "bidirectional"))
    )
    (net (code "16") (name "INT_RTC") (class "Default")
      (node (ref "R1_PINH1") (pin "1") (pinfunction "1_1") (pintype "passive"))
      (node (ref "TP5") (pin "TP") (pinfunction "TP_TP") (pintype "input"))
      (node (ref "U1") (pin "8") (pinfunction "IO0_8") (pintype "bidirectional"))
      (node (ref "U3") (pin "3") (pinfunction "SQW/~{INT}_3") (pintype "output"))
    )
    (net (code "17") (name "IO{slash}BOOT") (class "Default")
      (node (ref "BOOT_BUTTON") (pin "3") (pinfunction "3_3") (pintype "passive"))
      (node (ref "BOOT_BUTTON") (pin "4") (pinfunction "4_4") (pintype "passive"))
      (node (ref "C6") (pin "1") (pinfunction "1_1") (pintype "passive"))
      (node (ref "R_BUTTON") (pin "2") (pinfunction "2_2") (pintype "passive"))
      (node (ref "U1") (pin "15") (pinfunction "IO9_15") (pintype "bidirectional"))
    )
    (net (code "18") (name "IO{slash}CHANGE") (class "Default")
      (node (ref "C10\\") (pin "1") (pinfunction "1_1") (pintype "passive"))
      (node (ref "CHANGE_BUTTON") (pin "3") (pinfunction "3_3") (pintype "passive"))
      (node (ref "CHANGE_BUTTON") (pin "4") (pinfunction "4_4") (pintype "passive"))
      (node (ref "R_CHANGE") (pin "2") (pinfunction "2_2") (pintype "passive"))
      (node (ref "U1") (pin "23") (pinfunction "IO15_23") (pintype "bidirectional"))
    )
    (net (code "19") (name "MISO") (class "Default")
      (node (ref "D12") (pin "1") (pinfunction "1_1") (pintype "passive"))
      (node (ref "R8") (pin "1") (pinfunction "1_1") (pintype "passive"))
      (node (ref "TP6") (pin "TP") (pinfunction "TP_TP") (pintype "input"))
      (node (ref "U1") (pin "27") (pinfunction "IO2_27") (pintype "bidirectional"))
      (node (ref "U2") (pin "P7") (pinfunction "DAT0_P7") (pintype "bidirectional"))
      (node (ref "U7") (pin "2") (pinfunction "DO(IO1)_2") (pintype "bidirectional"))
    )
    (net (code "20") (name "MOSI") (class "Default")
      (node (ref "D11") (pin "1") (pinfunction "1_1") (pintype "passive"))
      (node (ref "J1") (pin "14") (pinfunction "14_14") (pintype "bidirectional"))
      (node (ref "R7") (pin "1") (pinfunction "1_1") (pintype "passive"))
      (node (ref "TP7") (pin "TP") (pinfunction "TP_TP") (pintype "input"))
      (node (ref "U1") (pin "7") (pinfunction "IO7_7") (pintype "bidirectional"))
      (node (ref "U2") (pin "P3") (pinfunction "CMD_P3") (pintype "bidirectional"))
      (node (ref "U7") (pin "5") (pinfunction "DI(IO0)_5") (pintype "bidirectional"))
    )
    (net (code "21") (name "Net-(CHG_LED-PadC)") (class "Default")
      (node (ref "CHG_LED") (pin "C") (pinfunction "C_C") (pintype "passive"))
      (node (ref "R1_BAT") (pin "2") (pinfunction "2_2") (pintype "passive"))
    )
    (net (code "22") (name "Net-(D2-CATHODE)") (class "Default")
      (node (ref "C1_BAT1") (pin "1") (pinfunction "1_1") (pintype "passive"))
      (node (ref "D2") (pin "1") (pinfunction "CATHODE_1") (pintype "bidirectional"))
      (node (ref "IC2") (pin "1") (pinfunction "VIN_1") (pintype "bidirectional"))
      (node (ref "IC2") (pin "3") (pinfunction "CE_3") (pintype "bidirectional"))
      (node (ref "Q1") (pin "2") (pinfunction "S_2") (pintype "bidirectional"))
    )
    (net (code "23") (name "Net-(D3-A)") (class "Default")
      (node (ref "C4") (pin "1") (pinfunction "1_1") (pintype "passive"))
      (node (ref "D3") (pin "2") (pinfunction "A_2") (pintype "bidirectional"))
      (node (ref "D4") (pin "1") (pinfunction "K_1") (pintype "bidirectional"))
    )
    (net (code "24") (name "Net-(D7-CATHODE)") (class "Default")
      (node (ref "D7") (pin "1") (pinfunction "CATHODE_1") (pintype "bidirectional"))
      (node (ref "R_CAPACITOR") (pin "1") (pinfunction "1_1") (pintype "passive"))
    )
    (net (code "25") (name "Net-(EPD_C1-Pad1)") (class "Default")
      (node (ref "EPD_C1") (pin "1") (pinfunction "1_1") (pintype "passive"))
      (node (ref "J1") (pin "4") (pinfunction "4_4") (pintype "bidirectional"))
    )
    (net (code "26") (name "Net-(EPD_C2-Pad1)") (class "Default")
      (node (ref "EPD_C2") (pin "1") (pinfunction "1_1") (pintype "passive"))
      (node (ref "J1") (pin "5") (pinfunction "5_5") (pintype "bidirectional"))
    )
    (net (code "27") (name "Net-(EPD_C6-Pad1)") (class "Default")
      (node (ref "EPD_C6") (pin "1") (pinfunction "1_1") (pintype "passive"))
      (node (ref "J1") (pin "18") (pinfunction "18_18") (pintype "bidirectional"))
    )
    (net (code "28") (name "Net-(EPD_C7-Pad1)") (class "Default")
      (node (ref "EPD_C7") (pin "1") (pinfunction "1_1") (pintype "passive"))
      (node (ref "J1") (pin "19") (pinfunction "19_19") (pintype "bidirectional"))
    )
    (net (code "29") (name "Net-(EPD_C8-Pad1)") (class "Default")
      (node (ref "EPD_C8") (pin "1") (pinfunction "1_1") (pintype "passive"))
      (node (ref "J1") (pin "20") (pinfunction "20_20") (pintype "bidirectional"))
    )
    (net (code "30") (name "Net-(EPD_C10-Pad1)") (class "Default")
      (node (ref "EPD_C10") (pin "1") (pinfunction "1_1") (pintype "passive"))
      (node (ref "J1") (pin "22") (pinfunction "22_22") (pintype "bidirectional"))
    )
    (net (code "31") (name "Net-(EPD_C12-Pad1)") (class "Default")
      (node (ref "EPD_C12") (pin "1") (pinfunction "1_1") (pintype "passive"))
      (node (ref "J1") (pin "24") (pinfunction "24_24") (pintype "bidirectional"))
    )
    (net (code "32") (name "Net-(IC1-CT)") (class "Default")
      (node (ref "C_DELAY") (pin "1") (pinfunction "1_1") (pintype "passive"))
      (node (ref "IC1") (pin "5") (pinfunction "CT_5") (pintype "bidirectional"))
    )
    (net (code "33") (name "Net-(J2-PadA5)") (class "Default")
      (node (ref "J2") (pin "A5") (pinfunction "A5_A5") (pintype "bidirectional"))
      (node (ref "R1-USB") (pin "2") (pinfunction "2_2") (pintype "passive"))
    )
    (net (code "34") (name "Net-(J2-PadB5)") (class "Default")
      (node (ref "J2") (pin "B5") (pinfunction "B5_B5") (pintype "bidirectional"))
      (node (ref "R2-USB") (pin "1") (pinfunction "1_1") (pintype "passive"))
    )
    (net (code "35") (name "Net-(MCP73831-PROG)") (class "Default")
      (node (ref "MCP73831") (pin "5") (pinfunction "PROG_5") (pintype "input"))
      (node (ref "R2_BAT") (pin "2") (pinfunction "2_2") (pintype "passive"))
    )
    (net (code "36") (name "Net-(MCP73831-STAT)") (class "Default")
      (node (ref "MCP73831") (pin "1") (pinfunction "STAT_1") (pintype "output"))
      (node (ref "R1_BAT") (pin "1") (pinfunction "1_1") (pintype "passive"))
    )
    (net (code "37") (name "PREVGH") (class "Default")
      (node (ref "D5") (pin "1") (pinfunction "K_1") (pintype "bidirectional"))
      (node (ref "EPD_C9") (pin "1") (pinfunction "1_1") (pintype "passive"))
      (node (ref "J1") (pin "21") (pinfunction "21_21") (pintype "bidirectional"))
    )
    (net (code "38") (name "PREVGL") (class "Default")
      (node (ref "D4") (pin "2") (pinfunction "A_2") (pintype "bidirectional"))
      (node (ref "EPD_C11") (pin "1") (pinfunction "1_1") (pintype "passive"))
      (node (ref "J1") (pin "23") (pinfunction "23_23") (pintype "bidirectional"))
    )
    (net (code "39") (name "RESE") (class "Default")
      (node (ref "J1") (pin "3") (pinfunction "3_3") (pintype "bidirectional"))
      (node (ref "Q3") (pin "2") (pinfunction "S_2") (pintype "bidirectional"))
      (node (ref "R3") (pin "2") (pinfunction "2_2") (pintype "passive"))
    )
    (net (code "40") (name "RESE'") (class "Default")
      (node (ref "R2") (pin "2") (pinfunction "2_2") (pintype "passive"))
      (node (ref "R3") (pin "1") (pinfunction "1_1") (pintype "passive"))
      (node (ref "SJ1") (pin "2") (pinfunction "2_2") (pintype "passive"))
    )
    (net (code "41") (name "RESET") (class "Default")
      (node (ref "C5") (pin "1") (pinfunction "1_1") (pintype "passive"))
      (node (ref "IC1") (pin "1") (pinfunction "VOUT_1") (pintype "bidirectional"))
      (node (ref "RESET_BUTTON") (pin "3") (pinfunction "3_3") (pintype "passive"))
      (node (ref "RESET_BUTTON") (pin "4") (pinfunction "4_4") (pintype "passive"))
      (node (ref "R_RESET") (pin "2") (pinfunction "2_2") (pintype "passive"))
      (node (ref "U1") (pin "3") (pinfunction "EN_3") (pintype "input"))
    )
    (net (code "42") (name "RTC_RST") (class "Default")
      (node (ref "U1") (pin "16") (pinfunction "IO18_16") (pintype "bidirectional"))
      (node (ref "U3") (pin "4") (pinfunction "~{RST}_4") (pintype "input"))
    )
    (net (code "43") (name "RX") (class "Default")
      (node (ref "TP12") (pin "TP") (pinfunction "TP_TP") (pintype "input"))
      (node (ref "U1") (pin "24") (pinfunction "RXD0/GPIO17_24") (pintype "bidirectional"))
    )
    (net (code "44") (name "SCK") (class "Default")
      (node (ref "D10") (pin "1") (pinfunction "1_1") (pintype "passive"))
      (node (ref "J1") (pin "13") (pinfunction "13_13") (pintype "bidirectional"))
      (node (ref "R6") (pin "1") (pinfunction "1_1") (pintype "passive"))
      (node (ref "TP8") (pin "TP") (pinfunction "TP_TP") (pintype "input"))
      (node (ref "U1") (pin "6") (pinfunction "IO6_6") (pintype "bidirectional"))
      (node (ref "U2") (pin "P5") (pinfunction "CLK_P5") (pintype "bidirectional"))
      (node (ref "U7") (pin "6") (pinfunction "CLK_6") (pintype "input"))
    )
    (net (code "45") (name "SCL") (class "Default")
      (node (ref "J3") (pin "4") (pinfunction "4_4") (pintype "passive"))
      (node (ref "R2_PINH") (pin "1") (pinfunction "1_1") (pintype "passive"))
      (node (ref "SENSOR2") (pin "4") (pinfunction "SCK_4") (pintype "input"))
      (node (ref "U1") (pin "20") (pinfunction "IO22_20") (pintype "bidirectional"))
      (node (ref "U3") (pin "16") (pinfunction "SCL_16") (pintype "input"))
      (node (ref "U5") (pin "7") (pinfunction "SCL_7") (pintype "input"))
    )
    (net (code "46") (name "SDA") (class "Default")
      (node (ref "J3") (pin "3") (pinfunction "3_3") (pintype "passive"))
      (node (ref "R1_PINH") (pin "1") (pinfunction "1_1") (pintype "passive"))
      (node (ref "SENSOR2") (pin "3") (pinfunction "SDI_3") (pintype "bidirectional"))
      (node (ref "U1") (pin "19") (pinfunction "IO21_19") (pintype "bidirectional"))
      (node (ref "U3") (pin "15") (pinfunction "SDA_15") (pintype "bidirectional"))
      (node (ref "U5") (pin "8") (pinfunction "SDA_8") (pintype "bidirectional"))
    )
    (net (code "47") (name "SRC") (class "Default")
      (node (ref "C4") (pin "2") (pinfunction "2_2") (pintype "passive"))
      (node (ref "D5") (pin "2") (pinfunction "A_2") (pintype "bidirectional"))
      (node (ref "L1") (pin "1") (pinfunction "1_1") (pintype "passive"))
      (node (ref "Q3") (pin "3") (pinfunction "D_3") (pintype "bidirectional"))
    )
    (net (code "48") (name "SS_SD") (class "Default")
      (node (ref "D8") (pin "1") (pinfunction "1_1") (pintype "passive"))
      (node (ref "R10") (pin "1") (pinfunction "1_1") (pintype "passive"))
      (node (ref "U1") (pin "4") (pinfunction "IO4_4") (pintype "bidirectional"))
      (node (ref "U2") (pin "P2") (pinfunction "CD/DAT3_P2") (pintype "bidirectional"))
    )
    (net (code "49") (name "TX") (class "Default")
      (node (ref "TP11") (pin "TP") (pinfunction "TP_TP") (pintype "input"))
      (node (ref "U1") (pin "25") (pinfunction "TXD0/GPIO16_25") (pintype "bidirectional"))
    )
    (net (code "50") (name "USB_D+") (class "Default")
      (node (ref "D1") (pin "1") (pinfunction "I/O1_1_1") (pintype "bidirectional"))
      (node (ref "U1") (pin "14") (pinfunction "IO13_14") (pintype "bidirectional"))
    )
    (net (code "51") (name "USB_D-") (class "Default")
      (node (ref "D1") (pin "3") (pinfunction "I/O2_1_3") (pintype "bidirectional"))
      (node (ref "U1") (pin "13") (pinfunction "IO12_13") (pintype "bidirectional"))
    )
    (net (code "52") (name "VBAT") (class "Default")
      (node (ref "C2_BAT") (pin "1") (pinfunction "1_1") (pintype "passive"))
      (node (ref "D2") (pin "2") (pinfunction "ANODE_2") (pintype "bidirectional"))
      (node (ref "MCP73831") (pin "3") (pinfunction "VBAT_3") (pintype "power_in"))
      (node (ref "Q1") (pin "1") (pinfunction "G_1") (pintype "bidirectional"))
      (node (ref "Q1") (pin "3") (pinfunction "D_3") (pintype "bidirectional"))
      (node (ref "R1_PWRUSB") (pin "2") (pinfunction "2_2") (pintype "passive"))
      (node (ref "TP13") (pin "TP") (pinfunction "TP_TP") (pintype "input"))
      (node (ref "U5") (pin "2") (pinfunction "CELL_2") (pintype "power_in"))
      (node (ref "U5") (pin "3") (pinfunction "VDD_3") (pintype "power_in"))
    )
    (net (code "53") (name "VBUS") (class "Default")
      (node (ref "C1_BAT") (pin "1") (pinfunction "1_1") (pintype "passive"))
      (node (ref "C4_USB") (pin "1") (pinfunction "1_1") (pintype "passive"))
      (node (ref "C5_USB") (pin "1") (pinfunction "1_1") (pintype "passive"))
      (node (ref "CHG_LED") (pin "A") (pinfunction "A_A") (pintype "passive"))
      (node (ref "D1") (pin "5") (pinfunction "VBUS_5") (pintype "bidirectional"))
      (node (ref "MCP73831") (pin "4") (pinfunction "VIN_4") (pintype "power_in"))
      (node (ref "TP4") (pin "TP") (pinfunction "TP_TP") (pintype "input"))
    )
    (net (code "54") (name "VRTC") (class "Default")
      (node (ref "C10_SUPERCAP") (pin "2") (pinfunction "2_2") (pintype "passive"))
      (node (ref "C8") (pin "1") (pinfunction "1_1") (pintype "passive"))
      (node (ref "R_CAPACITOR") (pin "2") (pinfunction "2_2") (pintype "passive"))
      (node (ref "U3") (pin "14") (pinfunction "VBAT_14") (pintype "power_in"))
    )
    (net (code "55") (name "VUSB") (class "Default")
      (node (ref "J2") (pin "A4") (pinfunction "A4_A4") (pintype "bidirectional"))
      (node (ref "J2") (pin "A9") (pinfunction "A9_A9") (pintype "bidirectional"))
      (node (ref "J2") (pin "B4") (pinfunction "B4_B4") (pintype "bidirectional"))
      (node (ref "J2") (pin "B9") (pinfunction "B9_B9") (pintype "bidirectional"))
      (node (ref "PFMF.050.1") (pin "1") (pinfunction "1_1") (pintype "passive"))
      (node (ref "PFMF.050.1") (pin "2") (pinfunction "2_2") (pintype "passive"))
    )
    (net (code "56") (name "unconnected-(IC1-NC-Pad4)") (class "Default")
      (node (ref "IC1") (pin "4") (pinfunction "NC_4") (pintype "no_connect"))
    )
    (net (code "57") (name "unconnected-(IC2-NC-Pad4)") (class "Default")
      (node (ref "IC2") (pin "4") (pinfunction "NC_4") (pintype "no_connect"))
    )
    (net (code "58") (name "unconnected-(J1-Pad1)") (class "Default")
      (node (ref "J1") (pin "1") (pinfunction "1_1") (pintype "bidirectional"))
    )
    (net (code "59") (name "unconnected-(J1-Pad6)") (class "Default")
      (node (ref "J1") (pin "6") (pinfunction "6_6") (pintype "bidirectional"))
    )
    (net (code "60") (name "unconnected-(J1-Pad7)") (class "Default")
      (node (ref "J1") (pin "7") (pinfunction "7_7") (pintype "bidirectional"))
    )
    (net (code "61") (name "unconnected-(J2-PadA8)") (class "Default")
      (node (ref "J2") (pin "A8") (pinfunction "A8_A8") (pintype "bidirectional"))
    )
    (net (code "62") (name "unconnected-(J2-PadB8)") (class "Default")
      (node (ref "J2") (pin "B8") (pinfunction "B8_B8") (pintype "bidirectional"))
    )
    (net (code "63") (name "unconnected-(U1-NC-Pad22)") (class "Default")
      (node (ref "U1") (pin "22") (pinfunction "NC_22") (pintype "no_connect"))
    )
    (net (code "64") (name "unconnected-(U2-DAT1-PadP8)") (class "Default")
      (node (ref "U2") (pin "P8") (pinfunction "DAT1_P8") (pintype "bidirectional"))
    )
    (net (code "65") (name "unconnected-(U2-DAT2-PadP1)") (class "Default")
      (node (ref "U2") (pin "P1") (pinfunction "DAT2_P1") (pintype "bidirectional"))
    )
    (net (code "66") (name "unconnected-(U2-DETECTION_1-PadS1)") (class "Default")
      (node (ref "U2") (pin "S1") (pinfunction "DETECTION_1_S1") (pintype "bidirectional"))
    )
    (net (code "67") (name "unconnected-(U2-DETECTION_2-PadS2)") (class "Default")
      (node (ref "U2") (pin "S2") (pinfunction "DETECTION_2_S2") (pintype "bidirectional"))
    )
    (net (code "68") (name "unconnected-(U5-~{ALERT}-Pad5)") (class "Default")
      (node (ref "U5") (pin "5") (pinfunction "~{ALERT}_5") (pintype "output"))
    )
  )
)
